# HTU21D_Breakout-NoBigSilk.net
KiCad netlist of a schematic drawn in EAGLE
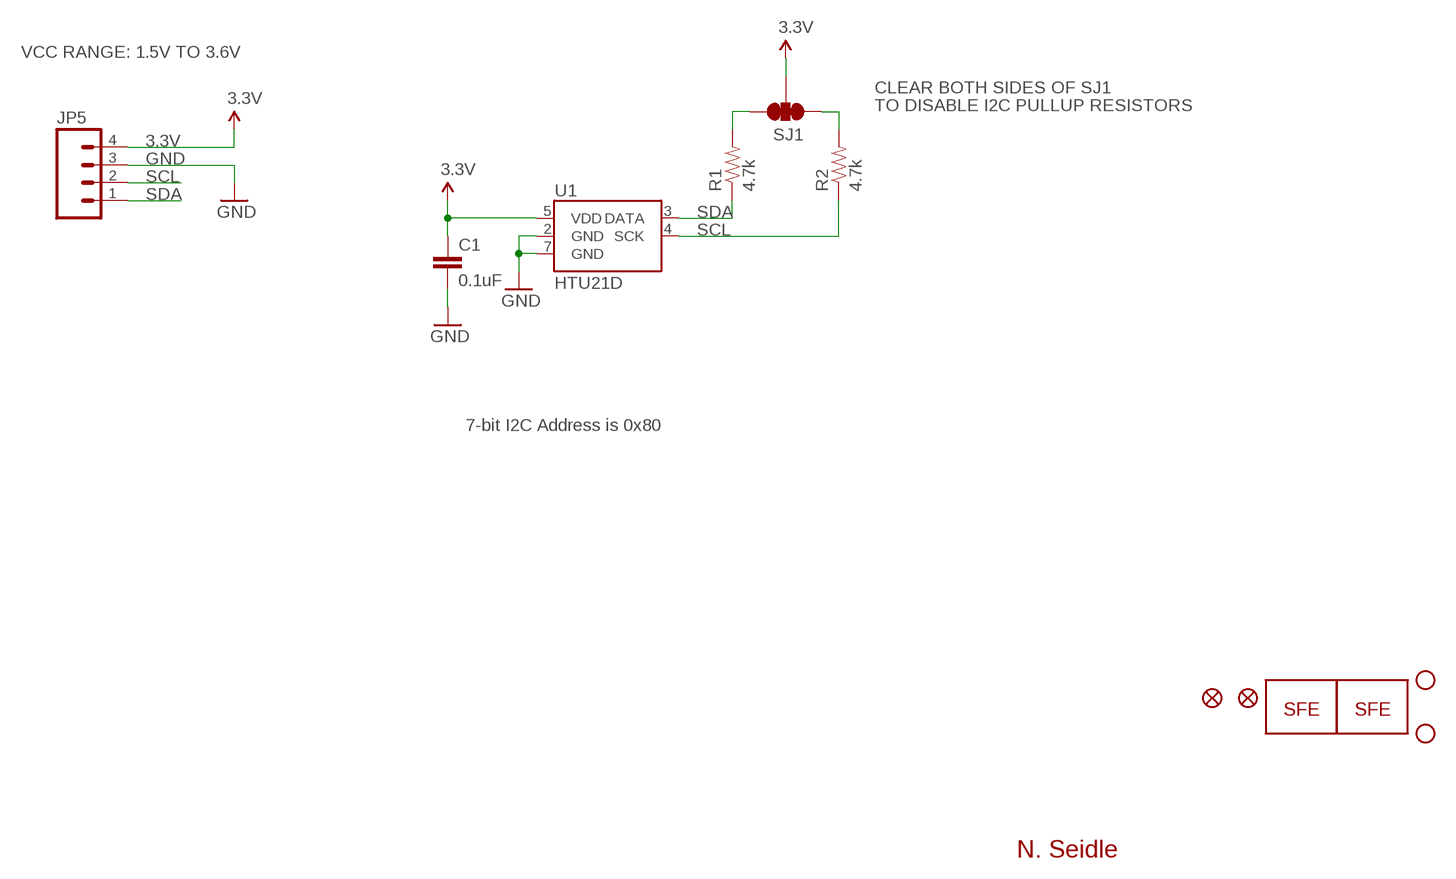
[diagram p0: schematic, sheet 1]

(export (version "E")
  (design (tool "Eeschema 10.0.6"))
  (components
    (comp (ref "C1")
      (value "0.1uF")
      (footprint "eagle-import:0402-CAP")
      (libsource (lib "eagle-import") (part "CAP0402-CAP"))
    )
    (comp (ref "JP2")
      (value "LOGO-SFENW2")
      (footprint "eagle-import:SFE-NEW-WEB")
      (libsource (lib "eagle-import") (part "SparkFun-Aesthetics_LOGO-SFENW2"))
    )
    (comp (ref "JP3")
      (value "FIDUCIALUFIDUCIAL")
      (footprint "eagle-import:MICRO-FIDUCIAL")
      (libsource (lib "eagle-import") (part "FIDUCIALUFIDUCIAL"))
    )
    (comp (ref "JP4")
      (value "FIDUCIALUFIDUCIAL")
      (footprint "eagle-import:MICRO-FIDUCIAL")
      (libsource (lib "eagle-import") (part "FIDUCIALUFIDUCIAL"))
    )
    (comp (ref "JP5")
      (value "M04PTH")
      (footprint "eagle-import:1X04")
      (libsource (lib "eagle-import") (part "M04PTH"))
    )
    (comp (ref "LOGO1")
      (value "LOGO-SFESK")
      (footprint "eagle-import:SFE-LOGO-FLAME")
      (libsource (lib "eagle-import") (part "LOGO-SFESK"))
    )
    (comp (ref "R1")
      (value "4.7k")
      (footprint "eagle-import:0402-RES")
      (libsource (lib "eagle-import") (part "RESISTOR0402-RES"))
    )
    (comp (ref "R2")
      (value "4.7k")
      (footprint "eagle-import:0402-RES")
      (libsource (lib "eagle-import") (part "RESISTOR0402-RES"))
    )
    (comp (ref "SJ1")
      (value "SOLDERJUMPER_2WAYPASTE1&2&3")
      (footprint "eagle-import:SJ_3_PASTE1&2&3")
      (libsource (lib "eagle-import") (part "SOLDERJUMPER_2WAYPASTE1&2&3"))
    )
    (comp (ref "STANDOFF1")
      (value "STAND-OFF")
      (footprint "eagle-import:STAND-OFF")
      (libsource (lib "eagle-import") (part "STAND-OFF"))
    )
    (comp (ref "STANDOFF2")
      (value "STAND-OFF")
      (footprint "eagle-import:STAND-OFF")
      (libsource (lib "eagle-import") (part "STAND-OFF"))
    )
    (comp (ref "U1")
      (value "HTU21D")
      (footprint "eagle-import:HTU21D")
      (libsource (lib "eagle-import") (part "HTU21DSMD"))
    )
  )
  (nets
    (net (code "1") (name "/SCL") (class "Default")
      (node (ref "JP5") (pin "2") (pinfunction "2_2") (pintype "passive"))
      (node (ref "R2") (pin "1") (pinfunction "1_1") (pintype "passive"))
      (node (ref "U1") (pin "4") (pinfunction "SCK_4") (pintype "input"))
    )
    (net (code "2") (name "/SDA") (class "Default")
      (node (ref "JP5") (pin "1") (pinfunction "1_1") (pintype "passive"))
      (node (ref "R1") (pin "1") (pinfunction "1_1") (pintype "passive"))
      (node (ref "U1") (pin "3") (pinfunction "DATA_3") (pintype "bidirectional"))
    )
    (net (code "3") (name "3.3V") (class "Default")
      (node (ref "C1") (pin "1") (pinfunction "1_1") (pintype "passive"))
      (node (ref "JP5") (pin "4") (pinfunction "4_4") (pintype "passive"))
      (node (ref "SJ1") (pin "2") (pinfunction "2_2") (pintype "passive"))
      (node (ref "U1") (pin "5") (pinfunction "VDD_5") (pintype "power_in"))
    )
    (net (code "4") (name "GND") (class "Default")
      (node (ref "C1") (pin "2") (pinfunction "2_2") (pintype "passive"))
      (node (ref "JP5") (pin "3") (pinfunction "3_3") (pintype "passive"))
      (node (ref "U1") (pin "2") (pinfunction "GND_2") (pintype "power_in"))
      (node (ref "U1") (pin "7") (pinfunction "GND_7") (pintype "power_in"))
    )
    (net (code "5") (name "Net-(R1-Pad2)") (class "Default")
      (node (ref "R1") (pin "2") (pinfunction "2_2") (pintype "passive"))
      (node (ref "SJ1") (pin "3") (pinfunction "3_3") (pintype "passive"))
    )
    (net (code "6") (name "Net-(R2-Pad2)") (class "Default")
      (node (ref "R2") (pin "2") (pinfunction "2_2") (pintype "passive"))
      (node (ref "SJ1") (pin "1") (pinfunction "1_1") (pintype "passive"))
    )
  )
)
